# Plasma_Speaker_SMD.net
KiCad netlist of a schematic drawn in Altium Designer
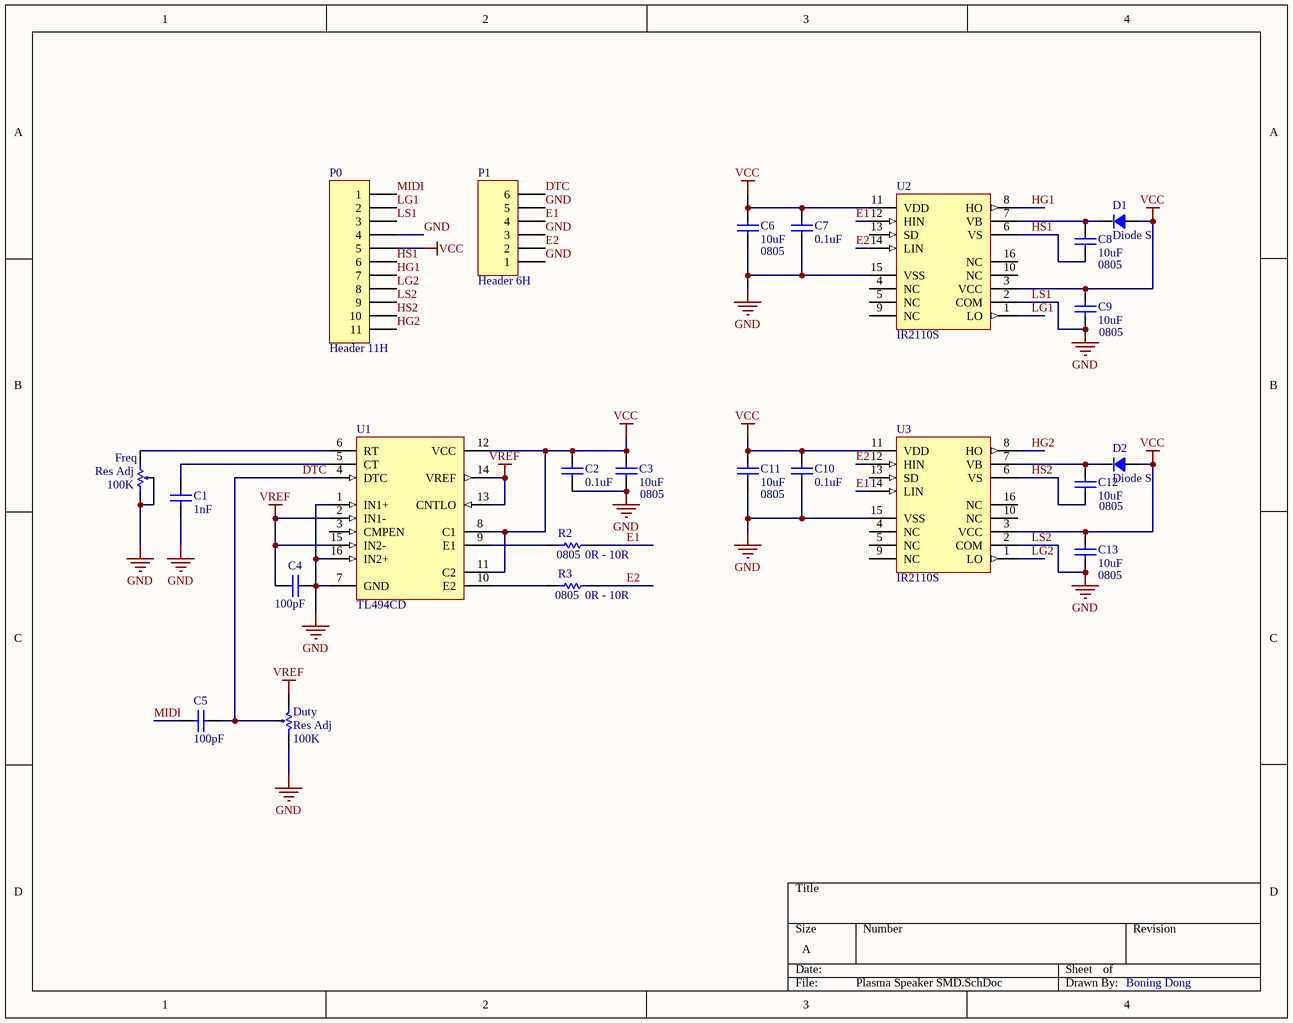
[diagram p0: Plasma Speaker SMD.SchDoc]

(export (version "E")
  (design (tool "Eeschema 10.0.6"))
  (components
    (comp (ref "C1")
      (value "1nF")
      (footprint "D0603")
      (description "Capacitor")
      (fields (field (name "Comment") "0603") (field (name "PUBLISHER") "Altium Limited"))
      (libsource (lib "Miscellaneous Devices") (part "Cap"))
    )
    (comp (ref "C2")
      (value "0.1uF")
      (footprint "D0603")
      (description "Capacitor")
      (fields (field (name "Comment") "0603") (field (name "PUBLISHER") "Altium Limited"))
      (libsource (lib "Miscellaneous Devices") (part "Cap"))
    )
    (comp (ref "C3")
      (value "0805")
      (footprint "D0805")
      (description "Capacitor")
      (fields (field (name "ALTIUM_VALUE") "10uF") (field (name "PUBLISHER") "Altium Limited"))
      (libsource (lib "Miscellaneous Devices") (part "Cap"))
    )
    (comp (ref "C4")
      (value "100pF")
      (footprint "D0603")
      (description "Capacitor")
      (fields (field (name "Comment") "0603") (field (name "PUBLISHER") "Altium Limited"))
      (libsource (lib "Miscellaneous Devices") (part "Cap"))
    )
    (comp (ref "C5")
      (value "100pF")
      (footprint "D0603")
      (description "Capacitor")
      (fields (field (name "Comment") "0603") (field (name "PUBLISHER") "Altium Limited"))
      (libsource (lib "Miscellaneous Devices") (part "Cap"))
    )
    (comp (ref "C6")
      (value "0805")
      (footprint "D0805")
      (description "Capacitor")
      (fields (field (name "ALTIUM_VALUE") "10uF") (field (name "PUBLISHER") "Altium Limited"))
      (libsource (lib "Miscellaneous Devices") (part "Cap"))
    )
    (comp (ref "C7")
      (value "0.1uF")
      (footprint "D0603")
      (description "Capacitor")
      (fields (field (name "Comment") "0603") (field (name "PUBLISHER") "Altium Limited"))
      (libsource (lib "Miscellaneous Devices") (part "Cap"))
    )
    (comp (ref "C8")
      (value "0805")
      (footprint "D0805")
      (description "Capacitor")
      (fields (field (name "ALTIUM_VALUE") "10uF") (field (name "PUBLISHER") "Altium Limited"))
      (libsource (lib "Miscellaneous Devices") (part "Cap"))
    )
    (comp (ref "C9")
      (value "0805")
      (footprint "D0805")
      (description "Capacitor")
      (fields (field (name "ALTIUM_VALUE") "10uF") (field (name "PUBLISHER") "Altium Limited"))
      (libsource (lib "Miscellaneous Devices") (part "Cap"))
    )
    (comp (ref "C10")
      (value "0.1uF")
      (footprint "D0603")
      (description "Capacitor")
      (fields (field (name "Comment") "0603") (field (name "PUBLISHER") "Altium Limited"))
      (libsource (lib "Miscellaneous Devices") (part "Cap"))
    )
    (comp (ref "C11")
      (value "0805")
      (footprint "D0805")
      (description "Capacitor")
      (fields (field (name "ALTIUM_VALUE") "10uF") (field (name "PUBLISHER") "Altium Limited"))
      (libsource (lib "Miscellaneous Devices") (part "Cap"))
    )
    (comp (ref "C12")
      (value "0805")
      (footprint "D0805")
      (description "Capacitor")
      (fields (field (name "ALTIUM_VALUE") "10uF") (field (name "PUBLISHER") "Altium Limited"))
      (libsource (lib "Miscellaneous Devices") (part "Cap"))
    )
    (comp (ref "C13")
      (value "0805")
      (footprint "D0805")
      (description "Capacitor")
      (fields (field (name "ALTIUM_VALUE") "10uF") (field (name "PUBLISHER") "Altium Limited"))
      (libsource (lib "Miscellaneous Devices") (part "Cap"))
    )
    (comp (ref "D1")
      (value "Diode S")
      (footprint "DO-214")
      (description "Zener Diode")
      (fields (field (name "PUBLISHER") "Altium Limited"))
      (libsource (lib "Miscellaneous Devices") (part "Diode S"))
    )
    (comp (ref "D2")
      (value "Diode S")
      (footprint "DO-214")
      (description "Zener Diode")
      (fields (field (name "PUBLISHER") "Altium Limited"))
      (libsource (lib "Miscellaneous Devices") (part "Diode S"))
    )
    (comp (ref "Duty")
      (value "Res Adj")
      (footprint "RES-3362P")
      (description "Resistor")
      (fields (field (name "ALTIUM_VALUE") "100K") (field (name "PUBLISHER") "Altium Limited"))
      (libsource (lib "Miscellaneous Devices") (part "Res Adj"))
    )
    (comp (ref "Freq")
      (value "Res Adj")
      (footprint "RES-3362P")
      (description "Resistor")
      (fields (field (name "ALTIUM_VALUE") "100K") (field (name "PUBLISHER") "Altium Limited"))
      (libsource (lib "Miscellaneous Devices") (part "Res Adj"))
    )
    (comp (ref "P0")
      (value "Header 11H")
      (footprint "HDR1X11H")
      (description "Header, 11-Pin, Right Angle")
      (fields (field (name "PUBLISHER") "Altium Limited"))
      (libsource (lib "Miscellaneous Connectors") (part "Header 11H"))
    )
    (comp (ref "P1")
      (value "Header 6H")
      (footprint "HDR1X6H")
      (description "Header, 6-Pin, Right Angle")
      (fields (field (name "PUBLISHER") "Altium Limited"))
      (libsource (lib "Miscellaneous Connectors") (part "Header 6H"))
    )
    (comp (ref "R2")
      (value "0805")
      (footprint "D0805")
      (description "Resistor")
      (fields (field (name "ALTIUM_VALUE") "0R - 10R") (field (name "PUBLISHER") "Altium Limited"))
      (libsource (lib "Miscellaneous Devices") (part "Res1"))
    )
    (comp (ref "R3")
      (value "0805")
      (footprint "D0805")
      (description "Resistor")
      (fields (field (name "ALTIUM_VALUE") "0R - 10R") (field (name "PUBLISHER") "Altium Limited"))
      (libsource (lib "Miscellaneous Devices") (part "Res1"))
    )
    (comp (ref "U1")
      (value "TL494CD")
      (footprint "751B-05_N")
      (description "Switchmode Pulse Width Modulation Control Circuit")
      (fields (field (name "PUBLISHER") "Altium Limited"))
      (libsource (lib "ON Semi Power Mgt SMPS Controller") (part "TL494CD"))
    )
    (comp (ref "U2")
      (value "IR2110S")
      (footprint "SOIC16_N")
      (description "High and Low Side Driver")
      (fields (field (name "PUBLISHER") "Altium Limited"))
      (libsource (lib "IR Interface Bridge Driver") (part "IR2110S"))
    )
    (comp (ref "U3")
      (value "IR2110S")
      (footprint "SOIC16_N")
      (description "High and Low Side Driver")
      (fields (field (name "PUBLISHER") "Altium Limited"))
      (libsource (lib "IR Interface Bridge Driver") (part "IR2110S"))
    )
  )
  (nets
    (net (code "1") (name "/DTC") (class "Default")
      (node (ref "C5") (pin "2") (pinfunction "2_2") (pintype "passive"))
      (node (ref "Duty") (pin "2") (pinfunction "2_2") (pintype "passive"))
      (node (ref "P1") (pin "6") (pinfunction "6_6") (pintype "passive"))
      (node (ref "U1") (pin "4") (pinfunction "DTC_4") (pintype "input"))
    )
    (net (code "2") (name "/E1") (class "Default")
      (node (ref "P1") (pin "4") (pinfunction "4_4") (pintype "passive"))
      (node (ref "R2") (pin "1") (pinfunction "1_1") (pintype "passive"))
      (node (ref "U2") (pin "12") (pinfunction "HIN_12") (pintype "input"))
      (node (ref "U3") (pin "14") (pinfunction "LIN_14") (pintype "input"))
    )
    (net (code "3") (name "/E2") (class "Default")
      (node (ref "P1") (pin "2") (pinfunction "2_2") (pintype "passive"))
      (node (ref "R3") (pin "1") (pinfunction "1_1") (pintype "passive"))
      (node (ref "U2") (pin "14") (pinfunction "LIN_14") (pintype "input"))
      (node (ref "U3") (pin "12") (pinfunction "HIN_12") (pintype "input"))
    )
    (net (code "4") (name "/HG1") (class "Default")
      (node (ref "P0") (pin "7") (pinfunction "7_7") (pintype "passive"))
      (node (ref "U2") (pin "8") (pinfunction "HO_8") (pintype "output"))
    )
    (net (code "5") (name "/HG2") (class "Default")
      (node (ref "P0") (pin "11") (pinfunction "11_11") (pintype "passive"))
      (node (ref "U3") (pin "8") (pinfunction "HO_8") (pintype "output"))
    )
    (net (code "6") (name "/HS1") (class "Default")
      (node (ref "C8") (pin "1") (pinfunction "1_1") (pintype "passive"))
      (node (ref "P0") (pin "6") (pinfunction "6_6") (pintype "passive"))
      (node (ref "U2") (pin "6") (pinfunction "VS_6") (pintype "power_in"))
    )
    (net (code "7") (name "/HS2") (class "Default")
      (node (ref "C12") (pin "1") (pinfunction "1_1") (pintype "passive"))
      (node (ref "P0") (pin "10") (pinfunction "10_10") (pintype "passive"))
      (node (ref "U3") (pin "6") (pinfunction "VS_6") (pintype "power_in"))
    )
    (net (code "8") (name "/LG1") (class "Default")
      (node (ref "P0") (pin "2") (pinfunction "2_2") (pintype "passive"))
      (node (ref "U2") (pin "1") (pinfunction "LO_1") (pintype "output"))
    )
    (net (code "9") (name "/LG2") (class "Default")
      (node (ref "P0") (pin "8") (pinfunction "8_8") (pintype "passive"))
      (node (ref "U3") (pin "1") (pinfunction "LO_1") (pintype "output"))
    )
    (net (code "10") (name "/MIDI") (class "Default")
      (node (ref "C5") (pin "1") (pinfunction "1_1") (pintype "passive"))
      (node (ref "P0") (pin "1") (pinfunction "1_1") (pintype "passive"))
    )
    (net (code "11") (name "GND") (class "Default")
      (node (ref "C1") (pin "1") (pinfunction "1_1") (pintype "passive"))
      (node (ref "C10") (pin "1") (pinfunction "1_1") (pintype "passive"))
      (node (ref "C11") (pin "1") (pinfunction "1_1") (pintype "passive"))
      (node (ref "C13") (pin "1") (pinfunction "1_1") (pintype "passive"))
      (node (ref "C2") (pin "1") (pinfunction "1_1") (pintype "passive"))
      (node (ref "C3") (pin "1") (pinfunction "1_1") (pintype "passive"))
      (node (ref "C4") (pin "1") (pinfunction "1_1") (pintype "passive"))
      (node (ref "C6") (pin "1") (pinfunction "1_1") (pintype "passive"))
      (node (ref "C7") (pin "1") (pinfunction "1_1") (pintype "passive"))
      (node (ref "C9") (pin "1") (pinfunction "1_1") (pintype "passive"))
      (node (ref "Duty") (pin "3") (pinfunction "3_3") (pintype "passive"))
      (node (ref "Freq") (pin "2") (pinfunction "2_2") (pintype "passive"))
      (node (ref "Freq") (pin "3") (pinfunction "3_3") (pintype "passive"))
      (node (ref "P0") (pin "3") (pinfunction "3_3") (pintype "passive"))
      (node (ref "P0") (pin "4") (pinfunction "4_4") (pintype "passive"))
      (node (ref "P0") (pin "9") (pinfunction "9_9") (pintype "passive"))
      (node (ref "P1") (pin "1") (pinfunction "1_1") (pintype "passive"))
      (node (ref "P1") (pin "3") (pinfunction "3_3") (pintype "passive"))
      (node (ref "P1") (pin "5") (pinfunction "5_5") (pintype "passive"))
      (node (ref "U1") (pin "1") (pinfunction "IN1+_1") (pintype "input"))
      (node (ref "U1") (pin "16") (pinfunction "IN2+_16") (pintype "input"))
      (node (ref "U1") (pin "7") (pinfunction "GND_7") (pintype "power_in"))
      (node (ref "U2") (pin "15") (pinfunction "VSS_15") (pintype "power_in"))
      (node (ref "U2") (pin "2") (pinfunction "COM_2") (pintype "power_in"))
      (node (ref "U3") (pin "15") (pinfunction "VSS_15") (pintype "power_in"))
      (node (ref "U3") (pin "2") (pinfunction "COM_2") (pintype "power_in"))
    )
    (net (code "12") (name "Net-(U1-CT)") (class "Default")
      (node (ref "C1") (pin "2") (pinfunction "2_2") (pintype "passive"))
      (node (ref "U1") (pin "5") (pinfunction "CT_5") (pintype "passive"))
    )
    (net (code "13") (name "Net-(U1-E1)") (class "Default")
      (node (ref "R2") (pin "2") (pinfunction "2_2") (pintype "passive"))
      (node (ref "U1") (pin "9") (pinfunction "E1_9") (pintype "passive"))
    )
    (net (code "14") (name "Net-(U1-E2)") (class "Default")
      (node (ref "R3") (pin "2") (pinfunction "2_2") (pintype "passive"))
      (node (ref "U1") (pin "10") (pinfunction "E2_10") (pintype "passive"))
    )
    (net (code "15") (name "Net-(U1-RT)") (class "Default")
      (node (ref "Freq") (pin "1") (pinfunction "1_1") (pintype "passive"))
      (node (ref "U1") (pin "6") (pinfunction "RT_6") (pintype "passive"))
    )
    (net (code "16") (name "Net-(U2-VB)") (class "Default")
      (node (ref "C8") (pin "2") (pinfunction "2_2") (pintype "passive"))
      (node (ref "D1") (pin "2") (pinfunction "2_2") (pintype "passive"))
      (node (ref "U2") (pin "7") (pinfunction "VB_7") (pintype "power_in"))
    )
    (net (code "17") (name "Net-(U3-VB)") (class "Default")
      (node (ref "C12") (pin "2") (pinfunction "2_2") (pintype "passive"))
      (node (ref "D2") (pin "2") (pinfunction "2_2") (pintype "passive"))
      (node (ref "U3") (pin "7") (pinfunction "VB_7") (pintype "power_in"))
    )
    (net (code "18") (name "VCC") (class "Default")
      (node (ref "C10") (pin "2") (pinfunction "2_2") (pintype "passive"))
      (node (ref "C11") (pin "2") (pinfunction "2_2") (pintype "passive"))
      (node (ref "C13") (pin "2") (pinfunction "2_2") (pintype "passive"))
      (node (ref "C2") (pin "2") (pinfunction "2_2") (pintype "passive"))
      (node (ref "C3") (pin "2") (pinfunction "2_2") (pintype "passive"))
      (node (ref "C6") (pin "2") (pinfunction "2_2") (pintype "passive"))
      (node (ref "C7") (pin "2") (pinfunction "2_2") (pintype "passive"))
      (node (ref "C9") (pin "2") (pinfunction "2_2") (pintype "passive"))
      (node (ref "D1") (pin "1") (pinfunction "1_1") (pintype "passive"))
      (node (ref "D2") (pin "1") (pinfunction "1_1") (pintype "passive"))
      (node (ref "P0") (pin "5") (pinfunction "5_5") (pintype "passive"))
      (node (ref "U1") (pin "11") (pinfunction "C2_11") (pintype "passive"))
      (node (ref "U1") (pin "12") (pinfunction "VCC_12") (pintype "power_in"))
      (node (ref "U1") (pin "8") (pinfunction "C1_8") (pintype "passive"))
      (node (ref "U2") (pin "11") (pinfunction "VDD_11") (pintype "power_in"))
      (node (ref "U2") (pin "3") (pinfunction "VCC_3") (pintype "power_in"))
      (node (ref "U3") (pin "11") (pinfunction "VDD_11") (pintype "power_in"))
      (node (ref "U3") (pin "3") (pinfunction "VCC_3") (pintype "power_in"))
    )
    (net (code "19") (name "VREF") (class "Default")
      (node (ref "C4") (pin "2") (pinfunction "2_2") (pintype "passive"))
      (node (ref "Duty") (pin "1") (pinfunction "1_1") (pintype "passive"))
      (node (ref "U1") (pin "13") (pinfunction "CNTLO_13") (pintype "input"))
      (node (ref "U1") (pin "14") (pinfunction "VREF_14") (pintype "output"))
      (node (ref "U1") (pin "15") (pinfunction "IN2-_15") (pintype "input"))
      (node (ref "U1") (pin "2") (pinfunction "IN1-_2") (pintype "input"))
    )
    (net (code "20") (name "unconnected-(U1-CMPEN-Pad3)") (class "Default")
      (node (ref "U1") (pin "3") (pinfunction "CMPEN_3") (pintype "input"))
    )
    (net (code "21") (name "unconnected-(U2-NC-Pad4)") (class "Default")
      (node (ref "U2") (pin "4") (pinfunction "NC_4") (pintype "passive"))
    )
    (net (code "22") (name "unconnected-(U2-NC-Pad5)") (class "Default")
      (node (ref "U2") (pin "5") (pinfunction "NC_5") (pintype "passive"))
    )
    (net (code "23") (name "unconnected-(U2-NC-Pad9)") (class "Default")
      (node (ref "U2") (pin "9") (pinfunction "NC_9") (pintype "passive"))
    )
    (net (code "24") (name "unconnected-(U2-NC-Pad10)") (class "Default")
      (node (ref "U2") (pin "10") (pinfunction "NC_10") (pintype "passive"))
    )
    (net (code "25") (name "unconnected-(U2-NC-Pad16)") (class "Default")
      (node (ref "U2") (pin "16") (pinfunction "NC_16") (pintype "passive"))
    )
    (net (code "26") (name "unconnected-(U2-SD-Pad13)") (class "Default")
      (node (ref "U2") (pin "13") (pinfunction "SD_13") (pintype "input"))
    )
    (net (code "27") (name "unconnected-(U3-NC-Pad4)") (class "Default")
      (node (ref "U3") (pin "4") (pinfunction "NC_4") (pintype "passive"))
    )
    (net (code "28") (name "unconnected-(U3-NC-Pad5)") (class "Default")
      (node (ref "U3") (pin "5") (pinfunction "NC_5") (pintype "passive"))
    )
    (net (code "29") (name "unconnected-(U3-NC-Pad9)") (class "Default")
      (node (ref "U3") (pin "9") (pinfunction "NC_9") (pintype "passive"))
    )
    (net (code "30") (name "unconnected-(U3-NC-Pad10)") (class "Default")
      (node (ref "U3") (pin "10") (pinfunction "NC_10") (pintype "passive"))
    )
    (net (code "31") (name "unconnected-(U3-NC-Pad16)") (class "Default")
      (node (ref "U3") (pin "16") (pinfunction "NC_16") (pintype "passive"))
    )
    (net (code "32") (name "unconnected-(U3-SD-Pad13)") (class "Default")
      (node (ref "U3") (pin "13") (pinfunction "SD_13") (pintype "input"))
    )
  )
)
